# 411.net
KiCad netlist of a schematic drawn in Altium Designer
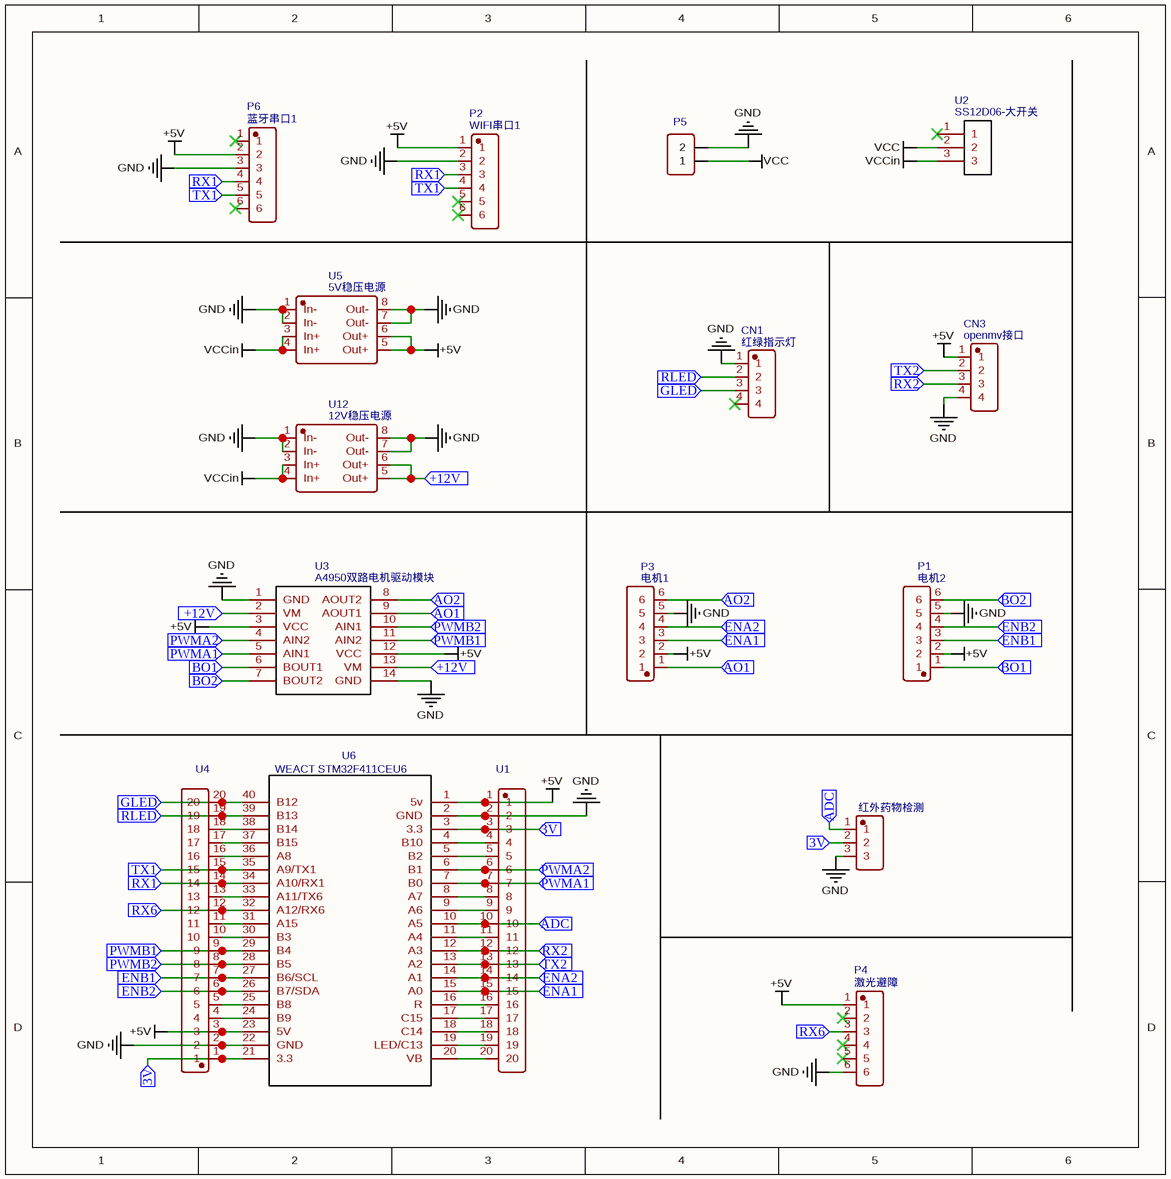
[diagram p0: 车身411.schdoc]

(export (version "E")
  (design (tool "Eeschema 10.0.6"))
  (components
    (comp (ref "1")
      (value "红外药物检测")
      (fields
        (field (name "BOM_SUPPLIER PART") "C9900002703")
        (field (name "BOM_MANUFACTURER PART") "PinSocket_1x03_P2.54mm_Vertical")
        (field (name "CONTRIBUTOR") "LCSC")
      )
      (libsource (lib "altium-import") (part "root_0_红外药物检测_"))
    )
    (comp (ref "CN1")
      (value "红绿指示灯")
      (fields
        (field (name "BOM_SUPPLIER PART") "C9900002996")
        (field (name "BOM_MANUFACTURER PART") "JTAG")
        (field (name "CONTRIBUTOR") "LCSC")
      )
      (libsource (lib "altium-import") (part "root_0_红绿指示灯_"))
    )
    (comp (ref "CN3")
      (value "openmv接口")
      (fields
        (field (name "BOM_SUPPLIER PART") "C9900002996")
        (field (name "BOM_MANUFACTURER PART") "JTAG")
        (field (name "CONTRIBUTOR") "LCSC")
      )
      (libsource (lib "altium-import") (part "root_0_openmv接口_"))
    )
    (comp (ref "P1")
      (value "电机2")
      (fields
        (field (name "BOM_MANUFACTURER PART") "Female header 1*6p")
        (field (name "BOM_SUPPLIER PART") "C40877")
      )
      (libsource (lib "altium-import") (part "root_2_电机2_"))
    )
    (comp (ref "P2")
      (value "WIFI串口1")
      (fields
        (field (name "BOM_MANUFACTURER PART") "Female header 1*6p")
        (field (name "BOM_SUPPLIER PART") "C40877")
      )
      (libsource (lib "altium-import") (part "root_0_WIFI串口1_"))
    )
    (comp (ref "P3")
      (value "电机1")
      (fields
        (field (name "BOM_MANUFACTURER PART") "Female header 1*6p")
        (field (name "BOM_SUPPLIER PART") "C40877")
      )
      (libsource (lib "altium-import") (part "root_2_电机1_"))
    )
    (comp (ref "P4")
      (value "激光避障")
      (fields
        (field (name "BOM_MANUFACTURER PART") "Female header 1*6p")
        (field (name "BOM_SUPPLIER PART") "C40877")
      )
      (libsource (lib "altium-import") (part "root_0_激光避障_"))
    )
    (comp (ref "P5")
      (value "Header-Female-2.54_1x2")
      (fields
        (field (name "BOM_MANUFACTURER PART") "2.54-1*2PFemale")
        (field (name "BOM_SUPPLIER PART") "C49661")
      )
      (libsource (lib "altium-import") (part "root_2_Header-Female-2.54_1x2_"))
    )
    (comp (ref "P6")
      (value "蓝牙串口1")
      (fields
        (field (name "BOM_MANUFACTURER PART") "Female header 1*6p")
        (field (name "BOM_SUPPLIER PART") "C40877")
      )
      (libsource (lib "altium-import") (part "root_0_蓝牙串口1_"))
    )
    (comp (ref "U1")
      (value "PM254-1-20-Z-8.5")
      (fields (field (name "BOM_SUPPLIER PART") "C2897383") (field (name "CONTRIBUTOR") "LCSC"))
      (libsource (lib "altium-import") (part "root_0_PM254-1-20-Z-8.5_"))
    )
    (comp (ref "U2")
      (value "SS12D06-大开关")
      (fields (field (name "CONTRIBUTOR") "EDAERNaOH"))
      (libsource (lib "altium-import") (part "root_0_SS12D06-大开关_"))
    )
    (comp (ref "U3")
      (value "A4950双路电机驱动模块")
      (fields (field (name "CONTRIBUTOR") "youlikesoilove"))
      (libsource (lib "altium-import") (part "root_0_A4950双路电机驱动模块_"))
    )
    (comp (ref "U4")
      (value "PM254-1-20-Z-8.5")
      (fields (field (name "BOM_SUPPLIER PART") "C2897383") (field (name "CONTRIBUTOR") "LCSC"))
      (libsource (lib "altium-import") (part "root_2_PM254-1-20-Z-8.5_"))
    )
    (comp (ref "U5")
      (value "5V稳压电源")
      (fields (field (name "CONTRIBUTOR") "fu1fan"))
      (libsource (lib "altium-import") (part "root_0_5V稳压电源_"))
    )
    (comp (ref "U6")
      (value "WEACT STM32F411CEU6")
      (fields (field (name "CONTRIBUTOR") "LShang"))
      (libsource (lib "altium-import") (part "root_0_WEACT STM32F411CEU6_"))
    )
    (comp (ref "U12")
      (value "12V稳压电源")
      (fields (field (name "CONTRIBUTOR") "fu1fan"))
      (libsource (lib "altium-import") (part "root_0_12V稳压电源_"))
    )
  )
  (nets
    (net (code "1") (name "+5V") (class "Default")
      (node (ref "CN3") (pin "1") (pinfunction "1_1") (pintype "passive"))
      (node (ref "P1") (pin "2") (pinfunction "2_2") (pintype "passive"))
      (node (ref "P2") (pin "1") (pinfunction "1_1") (pintype "passive"))
      (node (ref "P3") (pin "2") (pinfunction "2_2") (pintype "passive"))
      (node (ref "P4") (pin "1") (pinfunction "1_1") (pintype "passive"))
      (node (ref "P6") (pin "2") (pinfunction "2_2") (pintype "passive"))
      (node (ref "U1") (pin "1") (pinfunction "1_1") (pintype "passive"))
      (node (ref "U3") (pin "12") (pinfunction "VCC_12") (pintype "passive"))
      (node (ref "U3") (pin "3") (pinfunction "VCC_3") (pintype "passive"))
      (node (ref "U4") (pin "3") (pinfunction "3_3") (pintype "passive"))
      (node (ref "U5") (pin "5") (pinfunction "Out+_5") (pintype "passive"))
      (node (ref "U5") (pin "6") (pinfunction "Out+_6") (pintype "passive"))
      (node (ref "U6") (pin "1") (pinfunction "5v_1") (pintype "passive"))
      (node (ref "U6") (pin "23") (pinfunction "5V_23") (pintype "passive"))
    )
    (net (code "2") (name "/+12V") (class "Default")
      (node (ref "U12") (pin "5") (pinfunction "Out+_5") (pintype "passive"))
      (node (ref "U12") (pin "6") (pinfunction "Out+_6") (pintype "passive"))
      (node (ref "U3") (pin "13") (pinfunction "VM_13") (pintype "passive"))
      (node (ref "U3") (pin "2") (pinfunction "VM_2") (pintype "passive"))
    )
    (net (code "3") (name "/3V") (class "Default")
      (node (ref "1") (pin "2") (pinfunction "2_2") (pintype "passive"))
      (node (ref "U1") (pin "3") (pinfunction "3_3") (pintype "passive"))
      (node (ref "U4") (pin "1") (pinfunction "1_1") (pintype "passive"))
      (node (ref "U6") (pin "21") (pinfunction "3.3_21") (pintype "passive"))
      (node (ref "U6") (pin "3") (pinfunction "3.3_3") (pintype "passive"))
    )
    (net (code "4") (name "/ADC") (class "Default")
      (node (ref "1") (pin "1") (pinfunction "1_1") (pintype "passive"))
      (node (ref "U1") (pin "10") (pinfunction "10_10") (pintype "passive"))
      (node (ref "U6") (pin "10") (pinfunction "A5_10") (pintype "passive"))
    )
    (net (code "5") (name "/AO1") (class "Default")
      (node (ref "P3") (pin "1") (pinfunction "1_1") (pintype "passive"))
      (node (ref "U3") (pin "9") (pinfunction "AOUT1_9") (pintype "passive"))
    )
    (net (code "6") (name "/AO2") (class "Default")
      (node (ref "P3") (pin "6") (pinfunction "6_6") (pintype "passive"))
      (node (ref "U3") (pin "8") (pinfunction "AOUT2_8") (pintype "passive"))
    )
    (net (code "7") (name "/BO1") (class "Default")
      (node (ref "P1") (pin "1") (pinfunction "1_1") (pintype "passive"))
      (node (ref "U3") (pin "6") (pinfunction "BOUT1_6") (pintype "passive"))
    )
    (net (code "8") (name "/BO2") (class "Default")
      (node (ref "P1") (pin "6") (pinfunction "6_6") (pintype "passive"))
      (node (ref "U3") (pin "7") (pinfunction "BOUT2_7") (pintype "passive"))
    )
    (net (code "9") (name "/ENA1") (class "Default")
      (node (ref "P3") (pin "3") (pinfunction "3_3") (pintype "passive"))
      (node (ref "U1") (pin "15") (pinfunction "15_15") (pintype "passive"))
      (node (ref "U6") (pin "15") (pinfunction "A0_15") (pintype "passive"))
    )
    (net (code "10") (name "/ENA2") (class "Default")
      (node (ref "P3") (pin "4") (pinfunction "4_4") (pintype "passive"))
      (node (ref "U1") (pin "14") (pinfunction "14_14") (pintype "passive"))
      (node (ref "U6") (pin "14") (pinfunction "A1_14") (pintype "passive"))
    )
    (net (code "11") (name "/ENB1") (class "Default")
      (node (ref "P1") (pin "3") (pinfunction "3_3") (pintype "passive"))
      (node (ref "U4") (pin "7") (pinfunction "7_7") (pintype "passive"))
      (node (ref "U6") (pin "27") (pinfunction "B6/SCL_27") (pintype "passive"))
    )
    (net (code "12") (name "/ENB2") (class "Default")
      (node (ref "P1") (pin "4") (pinfunction "4_4") (pintype "passive"))
      (node (ref "U4") (pin "6") (pinfunction "6_6") (pintype "passive"))
      (node (ref "U6") (pin "26") (pinfunction "B7/SDA_26") (pintype "passive"))
    )
    (net (code "13") (name "/GLED") (class "Default")
      (node (ref "CN1") (pin "3") (pinfunction "3_3") (pintype "passive"))
      (node (ref "U4") (pin "20") (pinfunction "20_20") (pintype "passive"))
      (node (ref "U6") (pin "40") (pinfunction "B12_40") (pintype "passive"))
    )
    (net (code "14") (name "/PWMA1") (class "Default")
      (node (ref "U1") (pin "7") (pinfunction "7_7") (pintype "passive"))
      (node (ref "U3") (pin "5") (pinfunction "AIN1_5") (pintype "passive"))
      (node (ref "U6") (pin "7") (pinfunction "B0_7") (pintype "passive"))
    )
    (net (code "15") (name "/PWMA2") (class "Default")
      (node (ref "U1") (pin "6") (pinfunction "6_6") (pintype "passive"))
      (node (ref "U3") (pin "4") (pinfunction "AIN2_4") (pintype "passive"))
      (node (ref "U6") (pin "6") (pinfunction "B1_6") (pintype "passive"))
    )
    (net (code "16") (name "/PWMB1") (class "Default")
      (node (ref "U3") (pin "11") (pinfunction "AIN2_11") (pintype "passive"))
      (node (ref "U4") (pin "9") (pinfunction "9_9") (pintype "passive"))
      (node (ref "U6") (pin "29") (pinfunction "B4_29") (pintype "passive"))
    )
    (net (code "17") (name "/PWMB2") (class "Default")
      (node (ref "U3") (pin "10") (pinfunction "AIN1_10") (pintype "passive"))
      (node (ref "U4") (pin "8") (pinfunction "8_8") (pintype "passive"))
      (node (ref "U6") (pin "28") (pinfunction "B5_28") (pintype "passive"))
    )
    (net (code "18") (name "/RLED") (class "Default")
      (node (ref "CN1") (pin "2") (pinfunction "2_2") (pintype "passive"))
      (node (ref "U4") (pin "19") (pinfunction "19_19") (pintype "passive"))
      (node (ref "U6") (pin "39") (pinfunction "B13_39") (pintype "passive"))
    )
    (net (code "19") (name "/RX1") (class "Default")
      (node (ref "P2") (pin "3") (pinfunction "3_3") (pintype "passive"))
      (node (ref "P6") (pin "4") (pinfunction "4_4") (pintype "passive"))
      (node (ref "U4") (pin "14") (pinfunction "14_14") (pintype "passive"))
      (node (ref "U6") (pin "34") (pinfunction "A10/RX1_34") (pintype "passive"))
    )
    (net (code "20") (name "/RX2") (class "Default")
      (node (ref "CN3") (pin "3") (pinfunction "3_3") (pintype "passive"))
      (node (ref "U1") (pin "12") (pinfunction "12_12") (pintype "passive"))
      (node (ref "U6") (pin "12") (pinfunction "A3_12") (pintype "passive"))
    )
    (net (code "21") (name "/RX6") (class "Default")
      (node (ref "P4") (pin "3") (pinfunction "3_3") (pintype "passive"))
      (node (ref "U4") (pin "12") (pinfunction "12_12") (pintype "passive"))
      (node (ref "U6") (pin "32") (pinfunction "A12/RX6_32") (pintype "passive"))
    )
    (net (code "22") (name "/TX1") (class "Default")
      (node (ref "P2") (pin "4") (pinfunction "4_4") (pintype "passive"))
      (node (ref "P6") (pin "5") (pinfunction "5_5") (pintype "passive"))
      (node (ref "U4") (pin "15") (pinfunction "15_15") (pintype "passive"))
      (node (ref "U6") (pin "35") (pinfunction "A9/TX1_35") (pintype "passive"))
    )
    (net (code "23") (name "/TX2") (class "Default")
      (node (ref "CN3") (pin "2") (pinfunction "2_2") (pintype "passive"))
      (node (ref "U1") (pin "13") (pinfunction "13_13") (pintype "passive"))
      (node (ref "U6") (pin "13") (pinfunction "A2_13") (pintype "passive"))
    )
    (net (code "24") (name "GND") (class "Default")
      (node (ref "1") (pin "3") (pinfunction "3_3") (pintype "passive"))
      (node (ref "CN1") (pin "1") (pinfunction "1_1") (pintype "passive"))
      (node (ref "CN3") (pin "4") (pinfunction "4_4") (pintype "passive"))
      (node (ref "P1") (pin "5") (pinfunction "5_5") (pintype "passive"))
      (node (ref "P2") (pin "2") (pinfunction "2_2") (pintype "passive"))
      (node (ref "P3") (pin "5") (pinfunction "5_5") (pintype "passive"))
      (node (ref "P4") (pin "6") (pinfunction "6_6") (pintype "passive"))
      (node (ref "P5") (pin "2") (pinfunction "2_2") (pintype "passive"))
      (node (ref "P6") (pin "3") (pinfunction "3_3") (pintype "passive"))
      (node (ref "U1") (pin "2") (pinfunction "2_2") (pintype "passive"))
      (node (ref "U12") (pin "1") (pinfunction "In-_1") (pintype "passive"))
      (node (ref "U12") (pin "2") (pinfunction "In-_2") (pintype "passive"))
      (node (ref "U12") (pin "7") (pinfunction "Out-_7") (pintype "passive"))
      (node (ref "U12") (pin "8") (pinfunction "Out-_8") (pintype "passive"))
      (node (ref "U3") (pin "1") (pinfunction "GND_1") (pintype "passive"))
      (node (ref "U3") (pin "14") (pinfunction "GND_14") (pintype "passive"))
      (node (ref "U4") (pin "2") (pinfunction "2_2") (pintype "passive"))
      (node (ref "U5") (pin "1") (pinfunction "In-_1") (pintype "passive"))
      (node (ref "U5") (pin "2") (pinfunction "In-_2") (pintype "passive"))
      (node (ref "U5") (pin "7") (pinfunction "Out-_7") (pintype "passive"))
      (node (ref "U5") (pin "8") (pinfunction "Out-_8") (pintype "passive"))
      (node (ref "U6") (pin "2") (pinfunction "GND_2") (pintype "passive"))
      (node (ref "U6") (pin "22") (pinfunction "GND_22") (pintype "passive"))
    )
    (net (code "25") (name "Net-(U6-A4)") (class "Default")
      (node (ref "U1") (pin "11") (pinfunction "11_11") (pintype "passive"))
      (node (ref "U6") (pin "11") (pinfunction "A4_11") (pintype "passive"))
    )
    (net (code "26") (name "Net-(U6-A6)") (class "Default")
      (node (ref "U1") (pin "9") (pinfunction "9_9") (pintype "passive"))
      (node (ref "U6") (pin "9") (pinfunction "A6_9") (pintype "passive"))
    )
    (net (code "27") (name "Net-(U6-A7)") (class "Default")
      (node (ref "U1") (pin "8") (pinfunction "8_8") (pintype "passive"))
      (node (ref "U6") (pin "8") (pinfunction "A7_8") (pintype "passive"))
    )
    (net (code "28") (name "Net-(U6-A8)") (class "Default")
      (node (ref "U4") (pin "16") (pinfunction "16_16") (pintype "passive"))
      (node (ref "U6") (pin "36") (pinfunction "A8_36") (pintype "passive"))
    )
    (net (code "29") (name "Net-(U6-A11{slash}TX6)") (class "Default")
      (node (ref "U4") (pin "13") (pinfunction "13_13") (pintype "passive"))
      (node (ref "U6") (pin "33") (pinfunction "A11/TX6_33") (pintype "passive"))
    )
    (net (code "30") (name "Net-(U6-A15)") (class "Default")
      (node (ref "U4") (pin "11") (pinfunction "11_11") (pintype "passive"))
      (node (ref "U6") (pin "31") (pinfunction "A15_31") (pintype "passive"))
    )
    (net (code "31") (name "Net-(U6-B2)") (class "Default")
      (node (ref "U1") (pin "5") (pinfunction "5_5") (pintype "passive"))
      (node (ref "U6") (pin "5") (pinfunction "B2_5") (pintype "passive"))
    )
    (net (code "32") (name "Net-(U6-B3)") (class "Default")
      (node (ref "U4") (pin "10") (pinfunction "10_10") (pintype "passive"))
      (node (ref "U6") (pin "30") (pinfunction "B3_30") (pintype "passive"))
    )
    (net (code "33") (name "Net-(U6-B8)") (class "Default")
      (node (ref "U4") (pin "5") (pinfunction "5_5") (pintype "passive"))
      (node (ref "U6") (pin "25") (pinfunction "B8_25") (pintype "passive"))
    )
    (net (code "34") (name "Net-(U6-B9)") (class "Default")
      (node (ref "U4") (pin "4") (pinfunction "4_4") (pintype "passive"))
      (node (ref "U6") (pin "24") (pinfunction "B9_24") (pintype "passive"))
    )
    (net (code "35") (name "Net-(U6-B10)") (class "Default")
      (node (ref "U1") (pin "4") (pinfunction "4_4") (pintype "passive"))
      (node (ref "U6") (pin "4") (pinfunction "B10_4") (pintype "passive"))
    )
    (net (code "36") (name "Net-(U6-B14)") (class "Default")
      (node (ref "U4") (pin "18") (pinfunction "18_18") (pintype "passive"))
      (node (ref "U6") (pin "38") (pinfunction "B14_38") (pintype "passive"))
    )
    (net (code "37") (name "Net-(U6-B15)") (class "Default")
      (node (ref "U4") (pin "17") (pinfunction "17_17") (pintype "passive"))
      (node (ref "U6") (pin "37") (pinfunction "B15_37") (pintype "passive"))
    )
    (net (code "38") (name "Net-(U6-C14)") (class "Default")
      (node (ref "U1") (pin "18") (pinfunction "18_18") (pintype "passive"))
      (node (ref "U6") (pin "18") (pinfunction "C14_18") (pintype "passive"))
    )
    (net (code "39") (name "Net-(U6-C15)") (class "Default")
      (node (ref "U1") (pin "17") (pinfunction "17_17") (pintype "passive"))
      (node (ref "U6") (pin "17") (pinfunction "C15_17") (pintype "passive"))
    )
    (net (code "40") (name "Net-(U6-LED{slash}C13)") (class "Default")
      (node (ref "U1") (pin "19") (pinfunction "19_19") (pintype "passive"))
      (node (ref "U6") (pin "19") (pinfunction "LED/C13_19") (pintype "passive"))
    )
    (net (code "41") (name "Net-(U6-R)") (class "Default")
      (node (ref "U1") (pin "16") (pinfunction "16_16") (pintype "passive"))
      (node (ref "U6") (pin "16") (pinfunction "R_16") (pintype "passive"))
    )
    (net (code "42") (name "Net-(U6-VB)") (class "Default")
      (node (ref "U1") (pin "20") (pinfunction "20_20") (pintype "passive"))
      (node (ref "U6") (pin "20") (pinfunction "VB_20") (pintype "passive"))
    )
    (net (code "43") (name "VCC") (class "Default")
      (node (ref "P5") (pin "1") (pinfunction "1_1") (pintype "passive"))
      (node (ref "U2") (pin "2") (pinfunction "2_2") (pintype "passive"))
    )
    (net (code "44") (name "VCCin") (class "Default")
      (node (ref "U12") (pin "3") (pinfunction "In+_3") (pintype "passive"))
      (node (ref "U12") (pin "4") (pinfunction "In+_4") (pintype "passive"))
      (node (ref "U2") (pin "3") (pinfunction "3_3") (pintype "passive"))
      (node (ref "U5") (pin "3") (pinfunction "In+_3") (pintype "passive"))
      (node (ref "U5") (pin "4") (pinfunction "In+_4") (pintype "passive"))
    )
    (net (code "45") (name "unconnected-(CN1-Pad4)") (class "Default")
      (node (ref "CN1") (pin "4") (pinfunction "4_4") (pintype "passive+no_connect"))
    )
    (net (code "46") (name "unconnected-(P2-Pad5)") (class "Default")
      (node (ref "P2") (pin "5") (pinfunction "5_5") (pintype "passive+no_connect"))
    )
    (net (code "47") (name "unconnected-(P2-Pad6)") (class "Default")
      (node (ref "P2") (pin "6") (pinfunction "6_6") (pintype "passive+no_connect"))
    )
    (net (code "48") (name "unconnected-(P4-Pad2)") (class "Default")
      (node (ref "P4") (pin "2") (pinfunction "2_2") (pintype "passive+no_connect"))
    )
    (net (code "49") (name "unconnected-(P4-Pad4)") (class "Default")
      (node (ref "P4") (pin "4") (pinfunction "4_4") (pintype "passive+no_connect"))
    )
    (net (code "50") (name "unconnected-(P4-Pad5)") (class "Default")
      (node (ref "P4") (pin "5") (pinfunction "5_5") (pintype "passive+no_connect"))
    )
    (net (code "51") (name "unconnected-(P6-Pad1)") (class "Default")
      (node (ref "P6") (pin "1") (pinfunction "1_1") (pintype "passive+no_connect"))
    )
    (net (code "52") (name "unconnected-(P6-Pad6)") (class "Default")
      (node (ref "P6") (pin "6") (pinfunction "6_6") (pintype "passive+no_connect"))
    )
    (net (code "53") (name "unconnected-(U2-Pad1)") (class "Default")
      (node (ref "U2") (pin "1") (pinfunction "1_1") (pintype "passive+no_connect"))
    )
  )
)
